# Cell_Monitor.net
KiCad netlist of a schematic drawn in Altium Designer
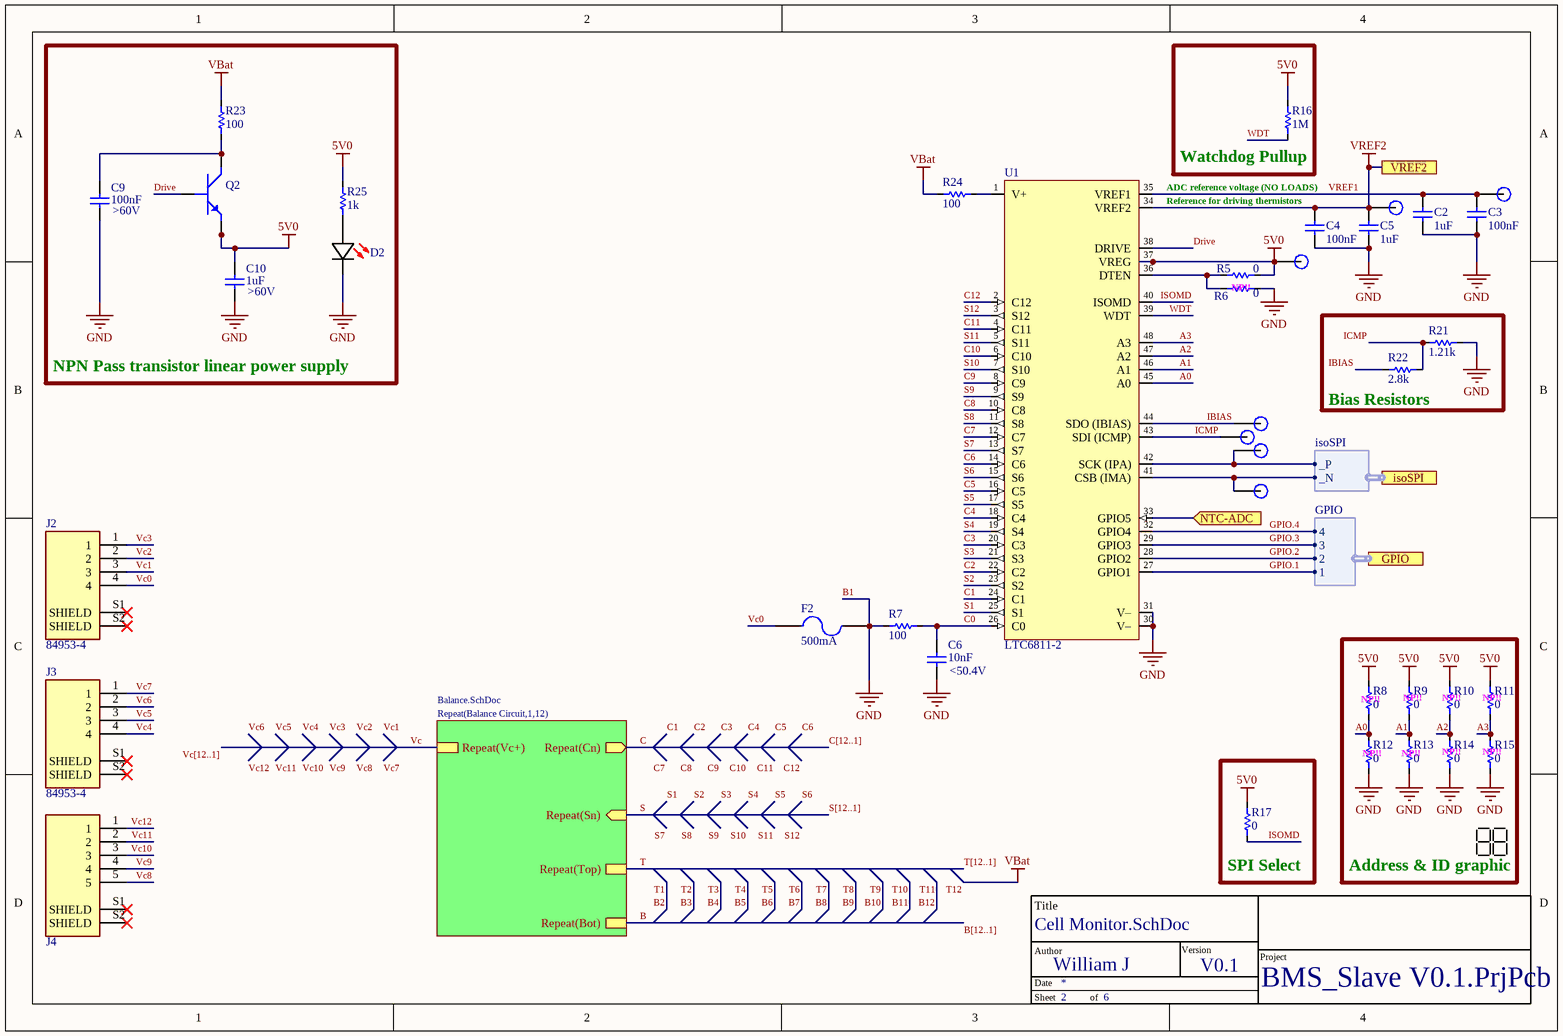
[diagram p0: Cell Monitor.SchDoc]

(export (version "E")
  (design (tool "Eeschema 10.0.6"))
  (components
    (comp (ref "C2")
      (value "1uF")
      (footprint "C-0402")
      (description "Capacitor")
      (fields (field (name "Comment") "C"))
      (libsource (lib "Passives") (part "Capacitor"))
    )
    (comp (ref "C3")
      (value "100nF")
      (footprint "C-0402")
      (description "Capacitor")
      (fields (field (name "Comment") "C"))
      (libsource (lib "Passives") (part "Capacitor"))
    )
    (comp (ref "C4")
      (value "100nF")
      (footprint "C-0402")
      (description "Capacitor")
      (fields (field (name "Comment") "C"))
      (libsource (lib "Passives") (part "Capacitor"))
    )
    (comp (ref "C5")
      (value "1uF")
      (footprint "C-0402")
      (description "Capacitor")
      (fields (field (name "Comment") "C"))
      (libsource (lib "Passives") (part "Capacitor"))
    )
    (comp (ref "C6")
      (value "10nF")
      (footprint "C_0603")
      (description "Capacitor")
      (fields (field (name "VOLTAGE") "<50.4V") (field (name "Comment") "C"))
      (libsource (lib "Passives") (part "Capacitor"))
    )
    (comp (ref "C9")
      (value "100nF")
      (footprint "C_0603")
      (description "Capacitor")
      (fields (field (name "VOLTAGE") ">60V") (field (name "Comment") "C"))
      (libsource (lib "Passives") (part "Capacitor"))
    )
    (comp (ref "C10")
      (value "1uF")
      (footprint "C_0603")
      (description "Capacitor")
      (fields (field (name "VOLTAGE") ">60V") (field (name "Comment") "C"))
      (libsource (lib "Passives") (part "Capacitor"))
    )
    (comp (ref "D2")
      (value "150060SS55040")
      (footprint "LED (0603)")
      (description "LED RED DIFFUSED 0603 SMD")
      (fields (field (name "MANUFACTURER") "Wurth Electronics"))
      (libsource (lib "LEDLib") (part "150060SS55040"))
    )
    (comp (ref "F2")
      (value "0466.500NR")
      (footprint "0466.500NR")
      (fields
        (field (name "MANUFACTURER") "Littelfuse")
        (field (name "CURRENT RATING") "500mA")
        (field (name "PUBLISHER") "Altium Limited")
      )
      (libsource (lib "Miscellaneous Devices") (part "Fuse 2"))
    )
    (comp (ref "J2")
      (value "84953-4")
      (footprint "84953-4")
      (fields (field (name "MF") "{'manufacturer': u'TE Connectivity'}"))
      (libsource (lib "TE_Con") (part "84953-4"))
    )
    (comp (ref "J3")
      (value "84953-4")
      (footprint "84953-4")
      (fields (field (name "MF") "{'manufacturer': u'TE Connectivity'}"))
      (libsource (lib "TE_Con") (part "84953-4"))
    )
    (comp (ref "J4") (value "84953-5") (footprint "84953-5") (libsource (lib "TE_Con") (part "84953-5")))
    (comp (ref "NT1") (value "NetTie") (footprint "NetTie") (libsource (lib "SchematicLib") (part "NetTie")))
    (comp (ref "NT2") (value "NetTie") (footprint "NetTie") (libsource (lib "SchematicLib") (part "NetTie")))
    (comp (ref "Q2")
      (value "PHPT60603NYX")
      (footprint "LFPAK56 (SOT669)")
      (description "60V, 3 A NPN high power bipolar transistor")
      (libsource (lib "SchematicLib") (part "PHPT60603NYX"))
    )
    (comp (ref "R5")
      (value "0")
      (footprint "R_0402")
      (description "Resistor")
      (libsource (lib "Passives") (part "Resistor"))
    )
    (comp (ref "R6")
      (value "0")
      (footprint "R_0402")
      (description "Resistor")
      (libsource (lib "Passives") (part "Resistor"))
    )
    (comp (ref "R7")
      (value "100")
      (footprint "R-0603")
      (description "Resistor")
      (libsource (lib "Passives") (part "Resistor"))
    )
    (comp (ref "R8")
      (value "0")
      (footprint "R_0402")
      (description "Resistor")
      (libsource (lib "Passives") (part "Resistor"))
    )
    (comp (ref "R9")
      (value "0")
      (footprint "R_0402")
      (description "Resistor")
      (libsource (lib "Passives") (part "Resistor"))
    )
    (comp (ref "R10")
      (value "0")
      (footprint "R_0402")
      (description "Resistor")
      (libsource (lib "Passives") (part "Resistor"))
    )
    (comp (ref "R11")
      (value "0")
      (footprint "R_0402")
      (description "Resistor")
      (libsource (lib "Passives") (part "Resistor"))
    )
    (comp (ref "R12")
      (value "0")
      (footprint "R_0402")
      (description "Resistor")
      (libsource (lib "Passives") (part "Resistor"))
    )
    (comp (ref "R13")
      (value "0")
      (footprint "R_0402")
      (description "Resistor")
      (libsource (lib "Passives") (part "Resistor"))
    )
    (comp (ref "R14")
      (value "0")
      (footprint "R_0402")
      (description "Resistor")
      (libsource (lib "Passives") (part "Resistor"))
    )
    (comp (ref "R15")
      (value "0")
      (footprint "R_0402")
      (description "Resistor")
      (libsource (lib "Passives") (part "Resistor"))
    )
    (comp (ref "R16")
      (value "1M")
      (footprint "R_0402")
      (description "Resistor")
      (libsource (lib "Passives") (part "Resistor"))
    )
    (comp (ref "R17")
      (value "0")
      (footprint "R_0402")
      (description "Resistor")
      (libsource (lib "Passives") (part "Resistor"))
    )
    (comp (ref "R21")
      (value "1.21k")
      (footprint "R_0402")
      (description "Resistor")
      (libsource (lib "Passives") (part "Resistor"))
    )
    (comp (ref "R22")
      (value "2.8k")
      (footprint "R_0402")
      (description "Resistor")
      (libsource (lib "Passives") (part "Resistor"))
    )
    (comp (ref "R23")
      (value "100")
      (footprint "R_2010")
      (description "Resistor")
      (libsource (lib "Passives") (part "Resistor"))
    )
    (comp (ref "R24")
      (value "100")
      (footprint "R_2010")
      (description "Resistor")
      (libsource (lib "Passives") (part "Resistor"))
    )
    (comp (ref "R25")
      (value "1k")
      (footprint "R-0603")
      (description "Resistor")
      (libsource (lib "Passives") (part "Resistor"))
    )
    (comp (ref "S1")
      (value "2x7Segment")
      (footprint "2x7Segment")
      (libsource (lib "SchematicLib") (part "2x7Segment"))
    )
    (comp (ref "TP1")
      (value "VREF1")
      (footprint "Test Point")
      (description "1.2mm Test point")
      (libsource (lib "SchematicLib") (part "Test Point"))
    )
    (comp (ref "TP2")
      (value "VREF2")
      (footprint "Test Point")
      (description "1.2mm Test point")
      (libsource (lib "SchematicLib") (part "Test Point"))
    )
    (comp (ref "TP3")
      (value "5V0")
      (footprint "Test Point")
      (description "1.2mm Test point")
      (libsource (lib "SchematicLib") (part "Test Point"))
    )
    (comp (ref "TP4")
      (value "IBIAS")
      (footprint "Test Point")
      (description "1.2mm Test point")
      (libsource (lib "SchematicLib") (part "Test Point"))
    )
    (comp (ref "TP5")
      (value "ICMP")
      (footprint "Test Point")
      (description "1.2mm Test point")
      (libsource (lib "SchematicLib") (part "Test Point"))
    )
    (comp (ref "TP6")
      (value "IPA")
      (footprint "Test Point")
      (description "1.2mm Test point")
      (libsource (lib "SchematicLib") (part "Test Point"))
    )
    (comp (ref "TP7")
      (value "IMA")
      (footprint "Test Point")
      (description "1.2mm Test point")
      (libsource (lib "SchematicLib") (part "Test Point"))
    )
    (comp (ref "U1")
      (value "LTC6811-2")
      (footprint "SSOP50P780X200-48N")
      (description "12 Channel Multicell Battery Monitor with Addressable Interface")
      (libsource (lib "SchematicLib") (part "LTC6811-2"))
    )
  )
  (nets
    (net (code "3") (name "/A0") (class "Default")
      (node (ref "R12") (pin "2") (pinfunction "2_2") (pintype "passive"))
      (node (ref "R8") (pin "1") (pinfunction "1_1") (pintype "passive"))
      (node (ref "U1") (pin "45") (pinfunction "A0_45") (pintype "passive"))
    )
    (net (code "4") (name "/A1") (class "Default")
      (node (ref "R13") (pin "2") (pinfunction "2_2") (pintype "passive"))
      (node (ref "R9") (pin "1") (pinfunction "1_1") (pintype "passive"))
      (node (ref "U1") (pin "46") (pinfunction "A1_46") (pintype "passive"))
    )
    (net (code "5") (name "/A2") (class "Default")
      (node (ref "R10") (pin "1") (pinfunction "1_1") (pintype "passive"))
      (node (ref "R14") (pin "2") (pinfunction "2_2") (pintype "passive"))
      (node (ref "U1") (pin "47") (pinfunction "A2_47") (pintype "passive"))
    )
    (net (code "6") (name "/A3") (class "Default")
      (node (ref "R11") (pin "1") (pinfunction "1_1") (pintype "passive"))
      (node (ref "R15") (pin "2") (pinfunction "2_2") (pintype "passive"))
      (node (ref "U1") (pin "48") (pinfunction "A3_48") (pintype "passive"))
    )
    (net (code "8") (name "/B1") (class "Default") (node (ref "NT1") (pin "2") (pintype "passive")))
    (net (code "11") (name "/C0") (class "Default")
      (node (ref "C6") (pin "2") (pinfunction "2_2") (pintype "passive"))
      (node (ref "R7") (pin "2") (pinfunction "2_2") (pintype "passive"))
      (node (ref "U1") (pin "26") (pinfunction "C0_26") (pintype "input"))
    )
    (net (code "12") (name "/C1") (class "Default")
      (node (ref "U1") (pin "24") (pinfunction "C1_24") (pintype "input"))
    )
    (net (code "13") (name "/C2") (class "Default")
      (node (ref "U1") (pin "22") (pinfunction "C2_22") (pintype "input"))
    )
    (net (code "14") (name "/C3") (class "Default")
      (node (ref "U1") (pin "20") (pinfunction "C3_20") (pintype "input"))
    )
    (net (code "15") (name "/C4") (class "Default")
      (node (ref "U1") (pin "18") (pinfunction "C4_18") (pintype "input"))
    )
    (net (code "16") (name "/C5") (class "Default")
      (node (ref "U1") (pin "16") (pinfunction "C5_16") (pintype "input"))
    )
    (net (code "17") (name "/C6") (class "Default")
      (node (ref "U1") (pin "14") (pinfunction "C6_14") (pintype "input"))
    )
    (net (code "18") (name "/C7") (class "Default")
      (node (ref "U1") (pin "12") (pinfunction "C7_12") (pintype "input"))
    )
    (net (code "19") (name "/C8") (class "Default")
      (node (ref "U1") (pin "10") (pinfunction "C8_10") (pintype "input"))
    )
    (net (code "20") (name "/C9") (class "Default")
      (node (ref "U1") (pin "8") (pinfunction "C9_8") (pintype "input"))
    )
    (net (code "21") (name "/C10") (class "Default")
      (node (ref "U1") (pin "6") (pinfunction "C10_6") (pintype "input"))
    )
    (net (code "22") (name "/C11") (class "Default")
      (node (ref "U1") (pin "4") (pinfunction "C11_4") (pintype "input"))
    )
    (net (code "23") (name "/C12") (class "Default")
      (node (ref "U1") (pin "2") (pinfunction "C12_2") (pintype "input"))
    )
    (net (code "25") (name "/Drive") (class "Default")
      (node (ref "Q2") (pin "4") (pinfunction "Base_4") (pintype "passive"))
      (node (ref "U1") (pin "38") (pinfunction "DRIVE_38") (pintype "passive"))
    )
    (net (code "26") (name "/GPIO.1") (class "Default")
      (node (ref "U1") (pin "27") (pinfunction "GPIO1_27") (pintype "bidirectional"))
    )
    (net (code "27") (name "/GPIO.2") (class "Default")
      (node (ref "U1") (pin "28") (pinfunction "GPIO2_28") (pintype "bidirectional"))
    )
    (net (code "28") (name "/GPIO.3") (class "Default")
      (node (ref "U1") (pin "29") (pinfunction "GPIO3_29") (pintype "bidirectional"))
    )
    (net (code "29") (name "/GPIO.4") (class "Default")
      (node (ref "U1") (pin "32") (pinfunction "GPIO4_32") (pintype "bidirectional"))
    )
    (net (code "30") (name "/IBIAS") (class "Default")
      (node (ref "R22") (pin "1") (pinfunction "1_1") (pintype "passive"))
      (node (ref "TP4") (pin "1") (pinfunction "1_1") (pintype "passive"))
      (node (ref "U1") (pin "44") (pinfunction "SDO_(IBIAS)_44") (pintype "passive"))
    )
    (net (code "31") (name "/ICMP") (class "Default")
      (node (ref "R21") (pin "1") (pinfunction "1_1") (pintype "passive"))
      (node (ref "R22") (pin "2") (pinfunction "2_2") (pintype "passive"))
      (node (ref "TP5") (pin "1") (pinfunction "1_1") (pintype "passive"))
      (node (ref "U1") (pin "43") (pinfunction "SDI_(ICMP)_43") (pintype "passive"))
    )
    (net (code "32") (name "/ISOMD") (class "Default")
      (node (ref "R17") (pin "1") (pinfunction "1_1") (pintype "passive"))
      (node (ref "U1") (pin "40") (pinfunction "ISOMD_40") (pintype "passive"))
    )
    (net (code "33") (name "/NTC-ADC") (class "Default")
      (node (ref "U1") (pin "33") (pinfunction "GPIO5_33") (pintype "input"))
    )
    (net (code "35") (name "/S1") (class "Default")
      (node (ref "U1") (pin "25") (pinfunction "S1_25") (pintype "output"))
    )
    (net (code "36") (name "/S2") (class "Default")
      (node (ref "U1") (pin "23") (pinfunction "S2_23") (pintype "output"))
    )
    (net (code "37") (name "/S3") (class "Default")
      (node (ref "U1") (pin "21") (pinfunction "S3_21") (pintype "output"))
    )
    (net (code "38") (name "/S4") (class "Default")
      (node (ref "U1") (pin "19") (pinfunction "S4_19") (pintype "output"))
    )
    (net (code "39") (name "/S5") (class "Default")
      (node (ref "U1") (pin "17") (pinfunction "S5_17") (pintype "output"))
    )
    (net (code "40") (name "/S6") (class "Default")
      (node (ref "U1") (pin "15") (pinfunction "S6_15") (pintype "output"))
    )
    (net (code "41") (name "/S7") (class "Default")
      (node (ref "U1") (pin "13") (pinfunction "S7_13") (pintype "output"))
    )
    (net (code "42") (name "/S8") (class "Default")
      (node (ref "U1") (pin "11") (pinfunction "S8_11") (pintype "output"))
    )
    (net (code "43") (name "/S9") (class "Default")
      (node (ref "U1") (pin "9") (pinfunction "S9_9") (pintype "output"))
    )
    (net (code "44") (name "/S10") (class "Default")
      (node (ref "U1") (pin "7") (pinfunction "S10_7") (pintype "output"))
    )
    (net (code "45") (name "/S11") (class "Default")
      (node (ref "U1") (pin "5") (pinfunction "S11_5") (pintype "output"))
    )
    (net (code "46") (name "/S12") (class "Default")
      (node (ref "U1") (pin "3") (pinfunction "S12_3") (pintype "output"))
    )
    (net (code "60") (name "/T12") (class "Default") (node (ref "NT2") (pin "1") (pintype "passive")))
    (net (code "62") (name "/VREF1") (class "Default")
      (node (ref "C2") (pin "2") (pinfunction "2_2") (pintype "passive"))
      (node (ref "C3") (pin "2") (pinfunction "2_2") (pintype "passive"))
      (node (ref "TP1") (pin "1") (pinfunction "1_1") (pintype "passive"))
      (node (ref "U1") (pin "35") (pinfunction "VREF1_35") (pintype "power_in"))
    )
    (net (code "64") (name "/Vc0") (class "Default")
      (node (ref "F2") (pin "1") (pinfunction "1_1") (pintype "passive"))
      (node (ref "J2") (pin "4") (pinfunction "4_4") (pintype "passive"))
    )
    (net (code "65") (name "/Vc1") (class "Default")
      (node (ref "J2") (pin "3") (pinfunction "3_3") (pintype "passive"))
    )
    (net (code "66") (name "/Vc2") (class "Default")
      (node (ref "J2") (pin "2") (pinfunction "2_2") (pintype "passive"))
    )
    (net (code "67") (name "/Vc3") (class "Default")
      (node (ref "J2") (pin "1") (pinfunction "1_1") (pintype "passive"))
    )
    (net (code "68") (name "/Vc4") (class "Default")
      (node (ref "J3") (pin "4") (pinfunction "4_4") (pintype "passive"))
    )
    (net (code "69") (name "/Vc5") (class "Default")
      (node (ref "J3") (pin "3") (pinfunction "3_3") (pintype "passive"))
    )
    (net (code "70") (name "/Vc6") (class "Default")
      (node (ref "J3") (pin "2") (pinfunction "2_2") (pintype "passive"))
    )
    (net (code "71") (name "/Vc7") (class "Default")
      (node (ref "J3") (pin "1") (pinfunction "1_1") (pintype "passive"))
    )
    (net (code "72") (name "/Vc8") (class "Default")
      (node (ref "J4") (pin "5") (pinfunction "5_5") (pintype "passive"))
    )
    (net (code "73") (name "/Vc9") (class "Default")
      (node (ref "J4") (pin "4") (pinfunction "4_4") (pintype "passive"))
    )
    (net (code "74") (name "/Vc10") (class "Default")
      (node (ref "J4") (pin "3") (pinfunction "3_3") (pintype "passive"))
    )
    (net (code "75") (name "/Vc11") (class "Default")
      (node (ref "J4") (pin "2") (pinfunction "2_2") (pintype "passive"))
    )
    (net (code "76") (name "/Vc12") (class "Default")
      (node (ref "J4") (pin "1") (pinfunction "1_1") (pintype "passive"))
    )
    (net (code "78") (name "/WDT") (class "Default")
      (node (ref "R16") (pin "1") (pinfunction "1_1") (pintype "passive"))
      (node (ref "U1") (pin "39") (pinfunction "WDT_39") (pintype "passive"))
    )
    (net (code "81") (name "5V0") (class "Default")
      (node (ref "C10") (pin "2") (pinfunction "2_2") (pintype "passive"))
      (node (ref "Q2") (pin "1") (pinfunction "Emitter_1") (pintype "passive"))
      (node (ref "Q2") (pin "2") (pinfunction "Emitter_2") (pintype "passive"))
      (node (ref "Q2") (pin "3") (pinfunction "Emitter_3") (pintype "passive"))
      (node (ref "R10") (pin "2") (pinfunction "2_2") (pintype "passive"))
      (node (ref "R11") (pin "2") (pinfunction "2_2") (pintype "passive"))
      (node (ref "R16") (pin "2") (pinfunction "2_2") (pintype "passive"))
      (node (ref "R17") (pin "2") (pinfunction "2_2") (pintype "passive"))
      (node (ref "R25") (pin "2") (pinfunction "2_2") (pintype "passive"))
      (node (ref "R5") (pin "2") (pinfunction "2_2") (pintype "passive"))
      (node (ref "R8") (pin "2") (pinfunction "2_2") (pintype "passive"))
      (node (ref "R9") (pin "2") (pinfunction "2_2") (pintype "passive"))
      (node (ref "TP3") (pin "1") (pinfunction "1_1") (pintype "passive"))
      (node (ref "U1") (pin "37") (pinfunction "VREG_37") (pintype "power_in"))
    )
    (net (code "82") (name "GND") (class "Default")
      (node (ref "C10") (pin "1") (pinfunction "1_1") (pintype "passive"))
      (node (ref "C2") (pin "1") (pinfunction "1_1") (pintype "passive"))
      (node (ref "C3") (pin "1") (pinfunction "1_1") (pintype "passive"))
      (node (ref "C4") (pin "1") (pinfunction "1_1") (pintype "passive"))
      (node (ref "C5") (pin "1") (pinfunction "1_1") (pintype "passive"))
      (node (ref "C6") (pin "1") (pinfunction "1_1") (pintype "passive"))
      (node (ref "C9") (pin "1") (pinfunction "1_1") (pintype "passive"))
      (node (ref "D2") (pin "1") (pinfunction "K_1") (pintype "passive"))
      (node (ref "F2") (pin "2") (pinfunction "2_2") (pintype "passive"))
      (node (ref "NT1") (pin "1") (pintype "passive"))
      (node (ref "R12") (pin "1") (pinfunction "1_1") (pintype "passive"))
      (node (ref "R13") (pin "1") (pinfunction "1_1") (pintype "passive"))
      (node (ref "R14") (pin "1") (pinfunction "1_1") (pintype "passive"))
      (node (ref "R15") (pin "1") (pinfunction "1_1") (pintype "passive"))
      (node (ref "R21") (pin "2") (pinfunction "2_2") (pintype "passive"))
      (node (ref "R6") (pin "1") (pinfunction "1_1") (pintype "passive"))
      (node (ref "R7") (pin "1") (pinfunction "1_1") (pintype "passive"))
      (node (ref "U1") (pin "30") (pinfunction "V–_30") (pintype "power_in"))
      (node (ref "U1") (pin "31") (pinfunction "V–_31") (pintype "power_in"))
    )
    (net (code "83") (name "Net-(D2-A)") (class "Default")
      (node (ref "D2") (pin "2") (pinfunction "A_2") (pintype "passive"))
      (node (ref "R25") (pin "1") (pinfunction "1_1") (pintype "passive"))
    )
    (net (code "84") (name "Net-(Q2-Collector)") (class "Default")
      (node (ref "C9") (pin "2") (pinfunction "2_2") (pintype "passive"))
      (node (ref "Q2") (pin "5") (pinfunction "Collector_5") (pintype "passive"))
      (node (ref "R23") (pin "1") (pinfunction "1_1") (pintype "passive"))
    )
    (net (code "85") (name "Net-(U1-CSB_(IMA))") (class "Default")
      (node (ref "TP7") (pin "1") (pinfunction "1_1") (pintype "passive"))
      (node (ref "U1") (pin "41") (pinfunction "CSB_(IMA)_41") (pintype "bidirectional"))
    )
    (net (code "86") (name "Net-(U1-DTEN)") (class "Default")
      (node (ref "R5") (pin "1") (pinfunction "1_1") (pintype "passive"))
      (node (ref "R6") (pin "2") (pinfunction "2_2") (pintype "passive"))
      (node (ref "U1") (pin "36") (pinfunction "DTEN_36") (pintype "passive"))
    )
    (net (code "87") (name "Net-(U1-SCK_(IPA))") (class "Default")
      (node (ref "TP6") (pin "1") (pinfunction "1_1") (pintype "passive"))
      (node (ref "U1") (pin "42") (pinfunction "SCK_(IPA)_42") (pintype "bidirectional"))
    )
    (net (code "88") (name "Net-(U1-V+)") (class "Default")
      (node (ref "R24") (pin "1") (pinfunction "1_1") (pintype "passive"))
      (node (ref "U1") (pin "1") (pinfunction "V+_1") (pintype "power_in"))
    )
    (net (code "89") (name "VBat") (class "Default")
      (node (ref "NT2") (pin "2") (pintype "passive"))
      (node (ref "R23") (pin "2") (pinfunction "2_2") (pintype "passive"))
      (node (ref "R24") (pin "2") (pinfunction "2_2") (pintype "passive"))
    )
    (net (code "90") (name "VREF2") (class "Default")
      (node (ref "C4") (pin "2") (pinfunction "2_2") (pintype "passive"))
      (node (ref "C5") (pin "2") (pinfunction "2_2") (pintype "passive"))
      (node (ref "TP2") (pin "1") (pinfunction "1_1") (pintype "passive"))
      (node (ref "U1") (pin "34") (pinfunction "VREF2_34") (pintype "power_in"))
    )
    (net (code "91") (name "unconnected-(J2-SHIELD-PadS1)") (class "Default")
      (node (ref "J2") (pin "S1") (pinfunction "SHIELD_S1") (pintype "passive+no_connect"))
    )
    (net (code "92") (name "unconnected-(J2-SHIELD-PadS2)") (class "Default")
      (node (ref "J2") (pin "S2") (pinfunction "SHIELD_S2") (pintype "passive+no_connect"))
    )
    (net (code "93") (name "unconnected-(J3-SHIELD-PadS1)") (class "Default")
      (node (ref "J3") (pin "S1") (pinfunction "SHIELD_S1") (pintype "passive+no_connect"))
    )
    (net (code "94") (name "unconnected-(J3-SHIELD-PadS2)") (class "Default")
      (node (ref "J3") (pin "S2") (pinfunction "SHIELD_S2") (pintype "passive+no_connect"))
    )
    (net (code "95") (name "unconnected-(J4-SHIELD-PadS1)") (class "Default")
      (node (ref "J4") (pin "S1") (pinfunction "SHIELD_S1") (pintype "passive+no_connect"))
    )
    (net (code "96") (name "unconnected-(J4-SHIELD-PadS2)") (class "Default")
      (node (ref "J4") (pin "S2") (pinfunction "SHIELD_S2") (pintype "passive+no_connect"))
    )
  )
)
